# AgitPOV_WiFi.net
KiCad netlist of a schematic drawn in EAGLE
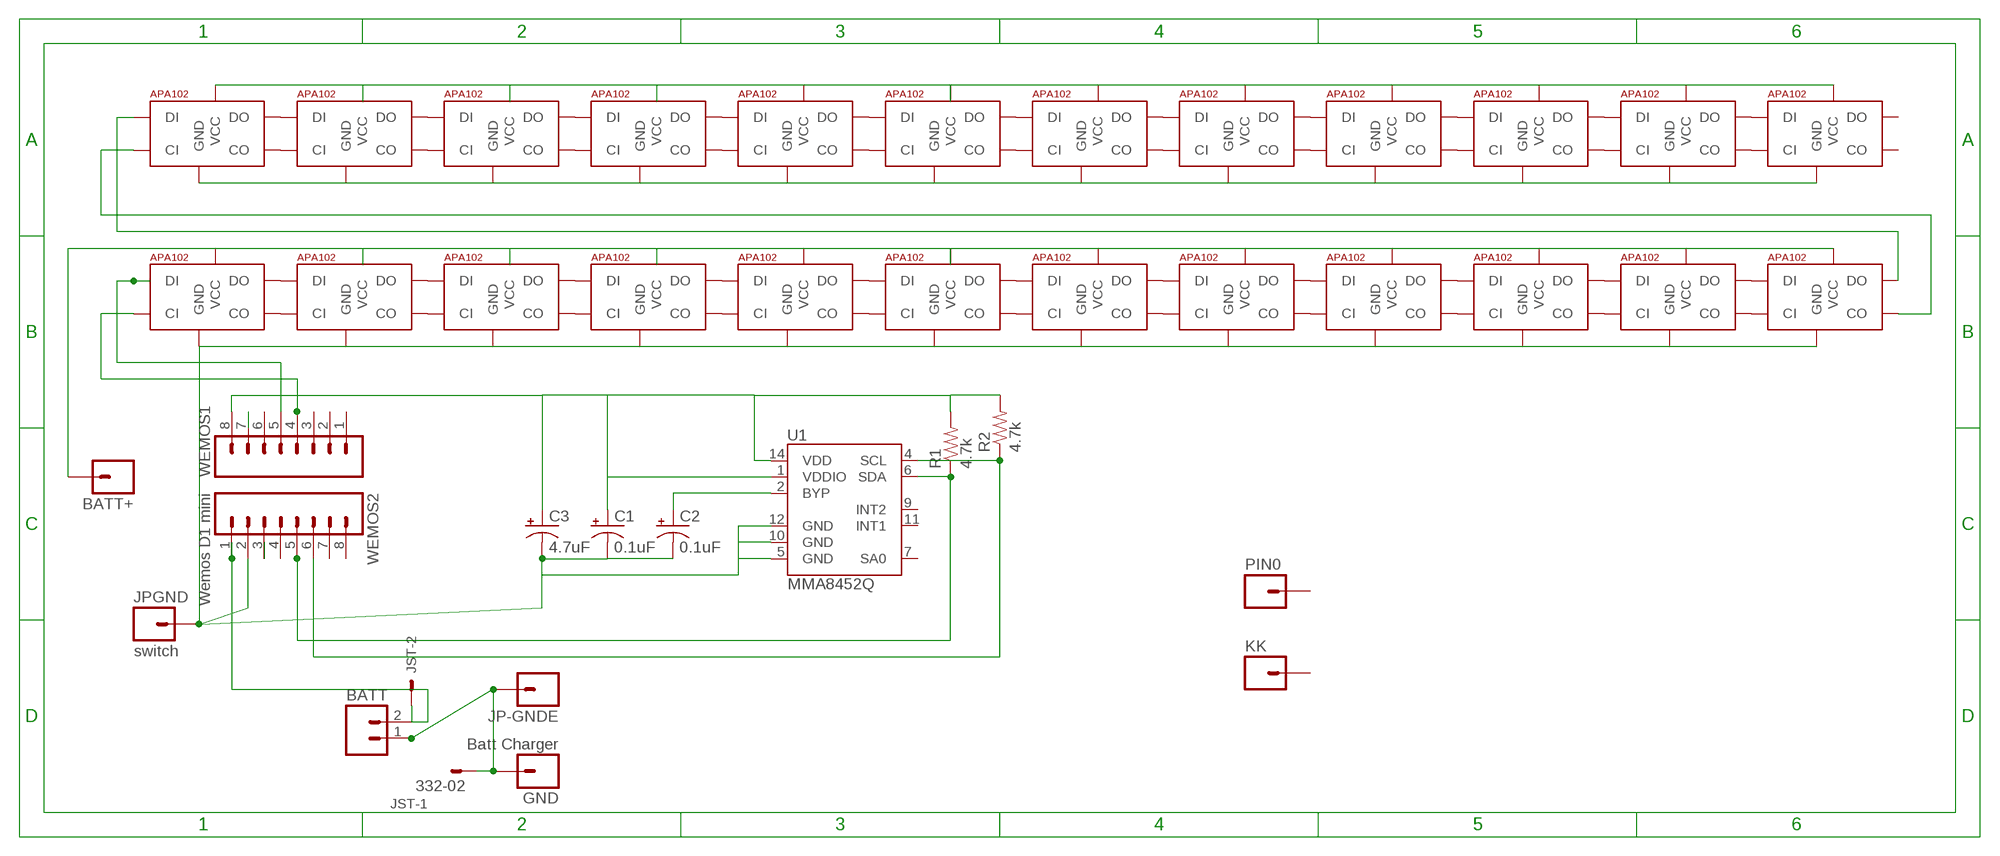
[diagram p0: schematic, sheet 1]

(export (version "E")
  (design (tool "Eeschema 10.0.6"))
  (components
    (comp (ref "BATT")
      (value "M02LOCK_LONGPADS")
      (footprint "eagle-import:1X02_LOCK_LONGPADS")
      (libsource (lib "eagle-import") (part "M02LOCK_LONGPADS"))
    )
    (comp (ref "BATT+")
      (value "M01PTH")
      (footprint "eagle-import:1X01")
      (libsource (lib "eagle-import") (part "M01PTH"))
    )
    (comp (ref "C1")
      (value "0.1uF")
      (footprint "eagle-import:EIA3216")
      (libsource (lib "eagle-import") (part "10UF-16V-10%(TANT)"))
    )
    (comp (ref "C2")
      (value "0.1uF")
      (footprint "eagle-import:EIA3216")
      (libsource (lib "eagle-import") (part "10UF-16V-10%(TANT)"))
    )
    (comp (ref "C3")
      (value "4.7uF")
      (footprint "eagle-import:EIA3216")
      (libsource (lib "eagle-import") (part "10UF-16V-10%(TANT)"))
    )
    (comp (ref "DEL1")
      (value "APA1025050")
      (footprint "eagle-import:APA102_5050")
      (libsource (lib "eagle-import") (part "APA1025050"))
    )
    (comp (ref "DEL2")
      (value "APA1025050")
      (footprint "eagle-import:APA102_5050")
      (libsource (lib "eagle-import") (part "APA1025050"))
    )
    (comp (ref "DEL3")
      (value "APA1025050")
      (footprint "eagle-import:APA102_5050")
      (libsource (lib "eagle-import") (part "APA1025050"))
    )
    (comp (ref "DEL4")
      (value "APA1025050")
      (footprint "eagle-import:APA102_5050")
      (libsource (lib "eagle-import") (part "APA1025050"))
    )
    (comp (ref "DEL5")
      (value "APA1025050")
      (footprint "eagle-import:APA102_5050")
      (libsource (lib "eagle-import") (part "APA1025050"))
    )
    (comp (ref "DEL6")
      (value "APA1025050")
      (footprint "eagle-import:APA102_5050")
      (libsource (lib "eagle-import") (part "APA1025050"))
    )
    (comp (ref "DEL7")
      (value "APA1025050")
      (footprint "eagle-import:APA102_5050")
      (libsource (lib "eagle-import") (part "APA1025050"))
    )
    (comp (ref "DEL8")
      (value "APA1025050")
      (footprint "eagle-import:APA102_5050")
      (libsource (lib "eagle-import") (part "APA1025050"))
    )
    (comp (ref "DEL9")
      (value "APA1025050")
      (footprint "eagle-import:APA102_5050")
      (libsource (lib "eagle-import") (part "APA1025050"))
    )
    (comp (ref "DEL10")
      (value "APA1025050")
      (footprint "eagle-import:APA102_5050")
      (libsource (lib "eagle-import") (part "APA1025050"))
    )
    (comp (ref "DEL11")
      (value "APA1025050")
      (footprint "eagle-import:APA102_5050")
      (libsource (lib "eagle-import") (part "APA1025050"))
    )
    (comp (ref "DEL12")
      (value "APA1025050")
      (footprint "eagle-import:APA102_5050")
      (libsource (lib "eagle-import") (part "APA1025050"))
    )
    (comp (ref "DEL13")
      (value "APA1025050")
      (footprint "eagle-import:APA102_5050")
      (libsource (lib "eagle-import") (part "APA1025050"))
    )
    (comp (ref "DEL15")
      (value "APA1025050")
      (footprint "eagle-import:APA102_5050")
      (libsource (lib "eagle-import") (part "APA1025050"))
    )
    (comp (ref "DEL16")
      (value "APA1025050")
      (footprint "eagle-import:APA102_5050")
      (libsource (lib "eagle-import") (part "APA1025050"))
    )
    (comp (ref "DEL17")
      (value "APA1025050")
      (footprint "eagle-import:APA102_5050")
      (libsource (lib "eagle-import") (part "APA1025050"))
    )
    (comp (ref "DEL18")
      (value "APA1025050")
      (footprint "eagle-import:APA102_5050")
      (libsource (lib "eagle-import") (part "APA1025050"))
    )
    (comp (ref "DEL19")
      (value "APA1025050")
      (footprint "eagle-import:APA102_5050")
      (libsource (lib "eagle-import") (part "APA1025050"))
    )
    (comp (ref "DEL20")
      (value "APA1025050")
      (footprint "eagle-import:APA102_5050")
      (libsource (lib "eagle-import") (part "APA1025050"))
    )
    (comp (ref "DEL21")
      (value "APA1025050")
      (footprint "eagle-import:APA102_5050")
      (libsource (lib "eagle-import") (part "APA1025050"))
    )
    (comp (ref "DEL22")
      (value "APA1025050")
      (footprint "eagle-import:APA102_5050")
      (libsource (lib "eagle-import") (part "APA1025050"))
    )
    (comp (ref "DEL23")
      (value "APA1025050")
      (footprint "eagle-import:APA102_5050")
      (libsource (lib "eagle-import") (part "APA1025050"))
    )
    (comp (ref "DEL24")
      (value "APA1025050")
      (footprint "eagle-import:APA102_5050")
      (libsource (lib "eagle-import") (part "APA1025050"))
    )
    (comp (ref "FFFFF")
      (value "APA1025050")
      (footprint "eagle-import:APA102_5050")
      (libsource (lib "eagle-import") (part "APA1025050"))
    )
    (comp (ref "GND")
      (value "Batt Charger")
      (footprint "eagle-import:1X01")
      (libsource (lib "eagle-import") (part "M01PTH"))
    )
    (comp (ref "JP-GNDE")
      (value "M01PTH")
      (footprint "eagle-import:1X01")
      (libsource (lib "eagle-import") (part "M01PTH"))
    )
    (comp (ref "JPGND")
      (value "switch")
      (footprint "eagle-import:1X01")
      (libsource (lib "eagle-import") (part "M01PTH"))
    )
    (comp (ref "JST")
      (value "332-02")
      (footprint "eagle-import:332-02")
      (libsource (lib "eagle-import") (part "332-02"))
    )
    (comp (ref "KK")
      (value "M01PTH")
      (footprint "eagle-import:1X01")
      (libsource (lib "eagle-import") (part "M01PTH"))
    )
    (comp (ref "PIN0")
      (value "M01PTH")
      (footprint "eagle-import:1X01")
      (libsource (lib "eagle-import") (part "M01PTH"))
    )
    (comp (ref "R1")
      (value "4.7k")
      (footprint "eagle-import:1206")
      (libsource (lib "eagle-import") (part "RESISTOR1206"))
    )
    (comp (ref "R2")
      (value "4.7k")
      (footprint "eagle-import:1206")
      (libsource (lib "eagle-import") (part "RESISTOR1206"))
    )
    (comp (ref "U1")
      (value "MMA8452Q")
      (footprint "eagle-import:QFN-16_0.5MM")
      (libsource (lib "eagle-import") (part "MMA8452Q"))
    )
    (comp (ref "WEMOS1")
      (value "M08")
      (footprint "eagle-import:1X08_ROUND")
      (libsource (lib "eagle-import") (part "M08"))
    )
    (comp (ref "WEMOS2")
      (value "Wemos D1 mini")
      (footprint "eagle-import:1X08_ROUND")
      (libsource (lib "eagle-import") (part "M08"))
    )
  )
  (nets
    (net (code "1") (name "/5V") (class "Default")
      (node (ref "BATT") (pin "2") (pinfunction "2_2") (pintype "passive"))
      (node (ref "BATT+") (pin "1") (pinfunction "1_1") (pintype "passive"))
      (node (ref "DEL1") (pin "1") (pinfunction "VCC_1") (pintype "bidirectional"))
      (node (ref "DEL10") (pin "1") (pinfunction "VCC_1") (pintype "bidirectional"))
      (node (ref "DEL11") (pin "1") (pinfunction "VCC_1") (pintype "bidirectional"))
      (node (ref "DEL12") (pin "1") (pinfunction "VCC_1") (pintype "bidirectional"))
      (node (ref "DEL13") (pin "1") (pinfunction "VCC_1") (pintype "bidirectional"))
      (node (ref "DEL15") (pin "1") (pinfunction "VCC_1") (pintype "bidirectional"))
      (node (ref "DEL16") (pin "1") (pinfunction "VCC_1") (pintype "bidirectional"))
      (node (ref "DEL17") (pin "1") (pinfunction "VCC_1") (pintype "bidirectional"))
      (node (ref "DEL18") (pin "1") (pinfunction "VCC_1") (pintype "bidirectional"))
      (node (ref "DEL19") (pin "1") (pinfunction "VCC_1") (pintype "bidirectional"))
      (node (ref "DEL2") (pin "1") (pinfunction "VCC_1") (pintype "bidirectional"))
      (node (ref "DEL20") (pin "1") (pinfunction "VCC_1") (pintype "bidirectional"))
      (node (ref "DEL21") (pin "1") (pinfunction "VCC_1") (pintype "bidirectional"))
      (node (ref "DEL22") (pin "1") (pinfunction "VCC_1") (pintype "bidirectional"))
      (node (ref "DEL23") (pin "1") (pinfunction "VCC_1") (pintype "bidirectional"))
      (node (ref "DEL24") (pin "1") (pinfunction "VCC_1") (pintype "bidirectional"))
      (node (ref "DEL3") (pin "1") (pinfunction "VCC_1") (pintype "bidirectional"))
      (node (ref "DEL4") (pin "1") (pinfunction "VCC_1") (pintype "bidirectional"))
      (node (ref "DEL5") (pin "1") (pinfunction "VCC_1") (pintype "bidirectional"))
      (node (ref "DEL6") (pin "1") (pinfunction "VCC_1") (pintype "bidirectional"))
      (node (ref "DEL7") (pin "1") (pinfunction "VCC_1") (pintype "bidirectional"))
      (node (ref "DEL8") (pin "1") (pinfunction "VCC_1") (pintype "bidirectional"))
      (node (ref "DEL9") (pin "1") (pinfunction "VCC_1") (pintype "bidirectional"))
      (node (ref "FFFFF") (pin "1") (pinfunction "VCC_1") (pintype "bidirectional"))
      (node (ref "JST") (pin "2") (pinfunction "S_2") (pintype "passive"))
      (node (ref "WEMOS2") (pin "1") (pinfunction "1_1") (pintype "passive"))
    )
    (net (code "2") (name "/GND") (class "Default")
      (node (ref "C1") (pin "C") (pinfunction "-_C") (pintype "passive"))
      (node (ref "C2") (pin "C") (pinfunction "-_C") (pintype "passive"))
      (node (ref "C3") (pin "C") (pinfunction "-_C") (pintype "passive"))
      (node (ref "DEL1") (pin "6") (pinfunction "GND_6") (pintype "bidirectional"))
      (node (ref "DEL10") (pin "6") (pinfunction "GND_6") (pintype "bidirectional"))
      (node (ref "DEL11") (pin "6") (pinfunction "GND_6") (pintype "bidirectional"))
      (node (ref "DEL12") (pin "6") (pinfunction "GND_6") (pintype "bidirectional"))
      (node (ref "DEL13") (pin "6") (pinfunction "GND_6") (pintype "bidirectional"))
      (node (ref "DEL15") (pin "6") (pinfunction "GND_6") (pintype "bidirectional"))
      (node (ref "DEL16") (pin "6") (pinfunction "GND_6") (pintype "bidirectional"))
      (node (ref "DEL17") (pin "6") (pinfunction "GND_6") (pintype "bidirectional"))
      (node (ref "DEL18") (pin "6") (pinfunction "GND_6") (pintype "bidirectional"))
      (node (ref "DEL19") (pin "6") (pinfunction "GND_6") (pintype "bidirectional"))
      (node (ref "DEL2") (pin "6") (pinfunction "GND_6") (pintype "bidirectional"))
      (node (ref "DEL20") (pin "6") (pinfunction "GND_6") (pintype "bidirectional"))
      (node (ref "DEL21") (pin "6") (pinfunction "GND_6") (pintype "bidirectional"))
      (node (ref "DEL22") (pin "6") (pinfunction "GND_6") (pintype "bidirectional"))
      (node (ref "DEL23") (pin "6") (pinfunction "GND_6") (pintype "bidirectional"))
      (node (ref "DEL24") (pin "6") (pinfunction "GND_6") (pintype "bidirectional"))
      (node (ref "DEL3") (pin "6") (pinfunction "GND_6") (pintype "bidirectional"))
      (node (ref "DEL4") (pin "6") (pinfunction "GND_6") (pintype "bidirectional"))
      (node (ref "DEL5") (pin "6") (pinfunction "GND_6") (pintype "bidirectional"))
      (node (ref "DEL6") (pin "6") (pinfunction "GND_6") (pintype "bidirectional"))
      (node (ref "DEL7") (pin "6") (pinfunction "GND_6") (pintype "bidirectional"))
      (node (ref "DEL8") (pin "6") (pinfunction "GND_6") (pintype "bidirectional"))
      (node (ref "DEL9") (pin "6") (pinfunction "GND_6") (pintype "bidirectional"))
      (node (ref "FFFFF") (pin "6") (pinfunction "GND_6") (pintype "bidirectional"))
      (node (ref "JPGND") (pin "1") (pinfunction "1_1") (pintype "passive"))
      (node (ref "U1") (pin "10") (pinfunction "GND_10") (pintype "bidirectional"))
      (node (ref "U1") (pin "12") (pinfunction "GND_12") (pintype "bidirectional"))
      (node (ref "U1") (pin "5") (pinfunction "GND_5") (pintype "bidirectional"))
      (node (ref "WEMOS2") (pin "2") (pinfunction "2_2") (pintype "passive"))
    )
    (net (code "3") (name "Net-(C1-+)") (class "Default")
      (node (ref "C1") (pin "A") (pinfunction "+_A") (pintype "passive"))
      (node (ref "C3") (pin "A") (pinfunction "+_A") (pintype "passive"))
      (node (ref "R1") (pin "2") (pinfunction "2_2") (pintype "passive"))
      (node (ref "R2") (pin "2") (pinfunction "2_2") (pintype "passive"))
      (node (ref "U1") (pin "1") (pinfunction "VDDIO_1") (pintype "bidirectional"))
      (node (ref "U1") (pin "14") (pinfunction "VDD_14") (pintype "bidirectional"))
      (node (ref "WEMOS1") (pin "8") (pinfunction "8_8") (pintype "passive"))
    )
    (net (code "4") (name "Net-(C2-+)") (class "Default")
      (node (ref "C2") (pin "A") (pinfunction "+_A") (pintype "passive"))
      (node (ref "U1") (pin "2") (pinfunction "BYP_2") (pintype "bidirectional"))
    )
    (net (code "5") (name "Net-(DEL1-CI)") (class "Default")
      (node (ref "DEL1") (pin "5") (pinfunction "CI_5") (pintype "bidirectional"))
      (node (ref "WEMOS1") (pin "4") (pinfunction "4_4") (pintype "passive"))
    )
    (net (code "6") (name "Net-(DEL1-CO)") (class "Default")
      (node (ref "DEL1") (pin "2") (pinfunction "CO_2") (pintype "bidirectional"))
      (node (ref "DEL2") (pin "5") (pinfunction "CI_5") (pintype "bidirectional"))
    )
    (net (code "7") (name "Net-(DEL1-DI)") (class "Default")
      (node (ref "DEL1") (pin "4") (pinfunction "DI_4") (pintype "bidirectional"))
      (node (ref "WEMOS1") (pin "5") (pinfunction "5_5") (pintype "passive"))
    )
    (net (code "8") (name "Net-(DEL1-DO)") (class "Default")
      (node (ref "DEL1") (pin "3") (pinfunction "DO_3") (pintype "bidirectional"))
      (node (ref "DEL2") (pin "4") (pinfunction "DI_4") (pintype "bidirectional"))
    )
    (net (code "9") (name "Net-(DEL2-CO)") (class "Default")
      (node (ref "DEL2") (pin "2") (pinfunction "CO_2") (pintype "bidirectional"))
      (node (ref "DEL3") (pin "5") (pinfunction "CI_5") (pintype "bidirectional"))
    )
    (net (code "10") (name "Net-(DEL2-DO)") (class "Default")
      (node (ref "DEL2") (pin "3") (pinfunction "DO_3") (pintype "bidirectional"))
      (node (ref "DEL3") (pin "4") (pinfunction "DI_4") (pintype "bidirectional"))
    )
    (net (code "11") (name "Net-(DEL3-CO)") (class "Default")
      (node (ref "DEL3") (pin "2") (pinfunction "CO_2") (pintype "bidirectional"))
      (node (ref "DEL4") (pin "5") (pinfunction "CI_5") (pintype "bidirectional"))
    )
    (net (code "12") (name "Net-(DEL3-DO)") (class "Default")
      (node (ref "DEL3") (pin "3") (pinfunction "DO_3") (pintype "bidirectional"))
      (node (ref "DEL4") (pin "4") (pinfunction "DI_4") (pintype "bidirectional"))
    )
    (net (code "13") (name "Net-(DEL4-CO)") (class "Default")
      (node (ref "DEL4") (pin "2") (pinfunction "CO_2") (pintype "bidirectional"))
      (node (ref "DEL5") (pin "5") (pinfunction "CI_5") (pintype "bidirectional"))
    )
    (net (code "14") (name "Net-(DEL4-DO)") (class "Default")
      (node (ref "DEL4") (pin "3") (pinfunction "DO_3") (pintype "bidirectional"))
      (node (ref "DEL5") (pin "4") (pinfunction "DI_4") (pintype "bidirectional"))
    )
    (net (code "15") (name "Net-(DEL5-CO)") (class "Default")
      (node (ref "DEL5") (pin "2") (pinfunction "CO_2") (pintype "bidirectional"))
      (node (ref "DEL6") (pin "5") (pinfunction "CI_5") (pintype "bidirectional"))
    )
    (net (code "16") (name "Net-(DEL5-DO)") (class "Default")
      (node (ref "DEL5") (pin "3") (pinfunction "DO_3") (pintype "bidirectional"))
      (node (ref "DEL6") (pin "4") (pinfunction "DI_4") (pintype "bidirectional"))
    )
    (net (code "17") (name "Net-(DEL6-CO)") (class "Default")
      (node (ref "DEL6") (pin "2") (pinfunction "CO_2") (pintype "bidirectional"))
      (node (ref "DEL7") (pin "5") (pinfunction "CI_5") (pintype "bidirectional"))
    )
    (net (code "18") (name "Net-(DEL6-DO)") (class "Default")
      (node (ref "DEL6") (pin "3") (pinfunction "DO_3") (pintype "bidirectional"))
      (node (ref "DEL7") (pin "4") (pinfunction "DI_4") (pintype "bidirectional"))
    )
    (net (code "19") (name "Net-(DEL7-CO)") (class "Default")
      (node (ref "DEL7") (pin "2") (pinfunction "CO_2") (pintype "bidirectional"))
      (node (ref "DEL8") (pin "5") (pinfunction "CI_5") (pintype "bidirectional"))
    )
    (net (code "20") (name "Net-(DEL7-DO)") (class "Default")
      (node (ref "DEL7") (pin "3") (pinfunction "DO_3") (pintype "bidirectional"))
      (node (ref "DEL8") (pin "4") (pinfunction "DI_4") (pintype "bidirectional"))
    )
    (net (code "21") (name "Net-(DEL8-CO)") (class "Default")
      (node (ref "DEL8") (pin "2") (pinfunction "CO_2") (pintype "bidirectional"))
      (node (ref "DEL9") (pin "5") (pinfunction "CI_5") (pintype "bidirectional"))
    )
    (net (code "22") (name "Net-(DEL8-DO)") (class "Default")
      (node (ref "DEL8") (pin "3") (pinfunction "DO_3") (pintype "bidirectional"))
      (node (ref "DEL9") (pin "4") (pinfunction "DI_4") (pintype "bidirectional"))
    )
    (net (code "23") (name "Net-(DEL10-CI)") (class "Default")
      (node (ref "DEL10") (pin "5") (pinfunction "CI_5") (pintype "bidirectional"))
      (node (ref "DEL9") (pin "2") (pinfunction "CO_2") (pintype "bidirectional"))
    )
    (net (code "24") (name "Net-(DEL10-CO)") (class "Default")
      (node (ref "DEL10") (pin "2") (pinfunction "CO_2") (pintype "bidirectional"))
      (node (ref "DEL11") (pin "5") (pinfunction "CI_5") (pintype "bidirectional"))
    )
    (net (code "25") (name "Net-(DEL10-DI)") (class "Default")
      (node (ref "DEL10") (pin "4") (pinfunction "DI_4") (pintype "bidirectional"))
      (node (ref "DEL9") (pin "3") (pinfunction "DO_3") (pintype "bidirectional"))
    )
    (net (code "26") (name "Net-(DEL10-DO)") (class "Default")
      (node (ref "DEL10") (pin "3") (pinfunction "DO_3") (pintype "bidirectional"))
      (node (ref "DEL11") (pin "4") (pinfunction "DI_4") (pintype "bidirectional"))
    )
    (net (code "27") (name "Net-(DEL11-CO)") (class "Default")
      (node (ref "DEL11") (pin "2") (pinfunction "CO_2") (pintype "bidirectional"))
      (node (ref "DEL12") (pin "5") (pinfunction "CI_5") (pintype "bidirectional"))
    )
    (net (code "28") (name "Net-(DEL11-DO)") (class "Default")
      (node (ref "DEL11") (pin "3") (pinfunction "DO_3") (pintype "bidirectional"))
      (node (ref "DEL12") (pin "4") (pinfunction "DI_4") (pintype "bidirectional"))
    )
    (net (code "29") (name "Net-(DEL12-CO)") (class "Default")
      (node (ref "DEL12") (pin "2") (pinfunction "CO_2") (pintype "bidirectional"))
      (node (ref "DEL13") (pin "5") (pinfunction "CI_5") (pintype "bidirectional"))
    )
    (net (code "30") (name "Net-(DEL12-DO)") (class "Default")
      (node (ref "DEL12") (pin "3") (pinfunction "DO_3") (pintype "bidirectional"))
      (node (ref "DEL13") (pin "4") (pinfunction "DI_4") (pintype "bidirectional"))
    )
    (net (code "31") (name "Net-(DEL13-CO)") (class "Default")
      (node (ref "DEL13") (pin "2") (pinfunction "CO_2") (pintype "bidirectional"))
      (node (ref "FFFFF") (pin "5") (pinfunction "CI_5") (pintype "bidirectional"))
    )
    (net (code "32") (name "Net-(DEL13-DO)") (class "Default")
      (node (ref "DEL13") (pin "3") (pinfunction "DO_3") (pintype "bidirectional"))
      (node (ref "FFFFF") (pin "4") (pinfunction "DI_4") (pintype "bidirectional"))
    )
    (net (code "33") (name "Net-(DEL15-CI)") (class "Default")
      (node (ref "DEL15") (pin "5") (pinfunction "CI_5") (pintype "bidirectional"))
      (node (ref "FFFFF") (pin "2") (pinfunction "CO_2") (pintype "bidirectional"))
    )
    (net (code "34") (name "Net-(DEL15-CO)") (class "Default")
      (node (ref "DEL15") (pin "2") (pinfunction "CO_2") (pintype "bidirectional"))
      (node (ref "DEL16") (pin "5") (pinfunction "CI_5") (pintype "bidirectional"))
    )
    (net (code "35") (name "Net-(DEL15-DI)") (class "Default")
      (node (ref "DEL15") (pin "4") (pinfunction "DI_4") (pintype "bidirectional"))
      (node (ref "FFFFF") (pin "3") (pinfunction "DO_3") (pintype "bidirectional"))
    )
    (net (code "36") (name "Net-(DEL15-DO)") (class "Default")
      (node (ref "DEL15") (pin "3") (pinfunction "DO_3") (pintype "bidirectional"))
      (node (ref "DEL16") (pin "4") (pinfunction "DI_4") (pintype "bidirectional"))
    )
    (net (code "37") (name "Net-(DEL16-CO)") (class "Default")
      (node (ref "DEL16") (pin "2") (pinfunction "CO_2") (pintype "bidirectional"))
      (node (ref "DEL17") (pin "5") (pinfunction "CI_5") (pintype "bidirectional"))
    )
    (net (code "38") (name "Net-(DEL16-DO)") (class "Default")
      (node (ref "DEL16") (pin "3") (pinfunction "DO_3") (pintype "bidirectional"))
      (node (ref "DEL17") (pin "4") (pinfunction "DI_4") (pintype "bidirectional"))
    )
    (net (code "39") (name "Net-(DEL17-CO)") (class "Default")
      (node (ref "DEL17") (pin "2") (pinfunction "CO_2") (pintype "bidirectional"))
      (node (ref "DEL18") (pin "5") (pinfunction "CI_5") (pintype "bidirectional"))
    )
    (net (code "40") (name "Net-(DEL17-DO)") (class "Default")
      (node (ref "DEL17") (pin "3") (pinfunction "DO_3") (pintype "bidirectional"))
      (node (ref "DEL18") (pin "4") (pinfunction "DI_4") (pintype "bidirectional"))
    )
    (net (code "41") (name "Net-(DEL18-CO)") (class "Default")
      (node (ref "DEL18") (pin "2") (pinfunction "CO_2") (pintype "bidirectional"))
      (node (ref "DEL19") (pin "5") (pinfunction "CI_5") (pintype "bidirectional"))
    )
    (net (code "42") (name "Net-(DEL18-DO)") (class "Default")
      (node (ref "DEL18") (pin "3") (pinfunction "DO_3") (pintype "bidirectional"))
      (node (ref "DEL19") (pin "4") (pinfunction "DI_4") (pintype "bidirectional"))
    )
    (net (code "43") (name "Net-(DEL19-CO)") (class "Default")
      (node (ref "DEL19") (pin "2") (pinfunction "CO_2") (pintype "bidirectional"))
      (node (ref "DEL20") (pin "5") (pinfunction "CI_5") (pintype "bidirectional"))
    )
    (net (code "44") (name "Net-(DEL19-DO)") (class "Default")
      (node (ref "DEL19") (pin "3") (pinfunction "DO_3") (pintype "bidirectional"))
      (node (ref "DEL20") (pin "4") (pinfunction "DI_4") (pintype "bidirectional"))
    )
    (net (code "45") (name "Net-(DEL20-CO)") (class "Default")
      (node (ref "DEL20") (pin "2") (pinfunction "CO_2") (pintype "bidirectional"))
      (node (ref "DEL21") (pin "5") (pinfunction "CI_5") (pintype "bidirectional"))
    )
    (net (code "46") (name "Net-(DEL20-DO)") (class "Default")
      (node (ref "DEL20") (pin "3") (pinfunction "DO_3") (pintype "bidirectional"))
      (node (ref "DEL21") (pin "4") (pinfunction "DI_4") (pintype "bidirectional"))
    )
    (net (code "47") (name "Net-(DEL21-CO)") (class "Default")
      (node (ref "DEL21") (pin "2") (pinfunction "CO_2") (pintype "bidirectional"))
      (node (ref "DEL22") (pin "5") (pinfunction "CI_5") (pintype "bidirectional"))
    )
    (net (code "48") (name "Net-(DEL21-DO)") (class "Default")
      (node (ref "DEL21") (pin "3") (pinfunction "DO_3") (pintype "bidirectional"))
      (node (ref "DEL22") (pin "4") (pinfunction "DI_4") (pintype "bidirectional"))
    )
    (net (code "49") (name "Net-(DEL22-CO)") (class "Default")
      (node (ref "DEL22") (pin "2") (pinfunction "CO_2") (pintype "bidirectional"))
      (node (ref "DEL23") (pin "5") (pinfunction "CI_5") (pintype "bidirectional"))
    )
    (net (code "50") (name "Net-(DEL22-DO)") (class "Default")
      (node (ref "DEL22") (pin "3") (pinfunction "DO_3") (pintype "bidirectional"))
      (node (ref "DEL23") (pin "4") (pinfunction "DI_4") (pintype "bidirectional"))
    )
    (net (code "51") (name "Net-(DEL23-CO)") (class "Default")
      (node (ref "DEL23") (pin "2") (pinfunction "CO_2") (pintype "bidirectional"))
      (node (ref "DEL24") (pin "5") (pinfunction "CI_5") (pintype "bidirectional"))
    )
    (net (code "52") (name "Net-(DEL23-DO)") (class "Default")
      (node (ref "DEL23") (pin "3") (pinfunction "DO_3") (pintype "bidirectional"))
      (node (ref "DEL24") (pin "4") (pinfunction "DI_4") (pintype "bidirectional"))
    )
    (net (code "53") (name "Net-(JSTA-S)") (class "Default")
      (node (ref "BATT") (pin "1") (pinfunction "1_1") (pintype "passive"))
      (node (ref "GND") (pin "1") (pinfunction "1_1") (pintype "passive"))
      (node (ref "JP-GNDE") (pin "1") (pinfunction "1_1") (pintype "passive"))
      (node (ref "JST") (pin "1") (pinfunction "S_1") (pintype "passive"))
    )
    (net (code "54") (name "Net-(U1-SCL)") (class "Default")
      (node (ref "R2") (pin "1") (pinfunction "1_1") (pintype "passive"))
      (node (ref "U1") (pin "4") (pinfunction "SCL_4") (pintype "bidirectional"))
      (node (ref "WEMOS2") (pin "6") (pinfunction "6_6") (pintype "passive"))
    )
    (net (code "55") (name "Net-(U1-SDA)") (class "Default")
      (node (ref "R1") (pin "1") (pinfunction "1_1") (pintype "passive"))
      (node (ref "U1") (pin "6") (pinfunction "SDA_6") (pintype "bidirectional"))
      (node (ref "WEMOS2") (pin "5") (pinfunction "5_5") (pintype "passive"))
    )
    (net (code "56") (name "unconnected-(DEL24-CO-Pad2)") (class "Default")
      (node (ref "DEL24") (pin "2") (pinfunction "CO_2") (pintype "bidirectional"))
    )
    (net (code "57") (name "unconnected-(DEL24-DO-Pad3)") (class "Default")
      (node (ref "DEL24") (pin "3") (pinfunction "DO_3") (pintype "bidirectional"))
    )
    (net (code "58") (name "unconnected-(KK-Pad1)") (class "Default")
      (node (ref "KK") (pin "1") (pinfunction "1_1") (pintype "passive"))
    )
    (net (code "59") (name "unconnected-(PIN0-Pad1)") (class "Default")
      (node (ref "PIN0") (pin "1") (pinfunction "1_1") (pintype "passive"))
    )
    (net (code "60") (name "unconnected-(U1-INT1-Pad11)") (class "Default")
      (node (ref "U1") (pin "11") (pinfunction "INT1_11") (pintype "bidirectional"))
    )
    (net (code "61") (name "unconnected-(U1-INT2-Pad9)") (class "Default")
      (node (ref "U1") (pin "9") (pinfunction "INT2_9") (pintype "bidirectional"))
    )
    (net (code "62") (name "unconnected-(U1-SA0-Pad7)") (class "Default")
      (node (ref "U1") (pin "7") (pinfunction "SA0_7") (pintype "bidirectional"))
    )
    (net (code "63") (name "unconnected-(WEMOS1-Pad1)") (class "Default")
      (node (ref "WEMOS1") (pin "1") (pinfunction "1_1") (pintype "passive"))
    )
    (net (code "64") (name "unconnected-(WEMOS1-Pad2)") (class "Default")
      (node (ref "WEMOS1") (pin "2") (pinfunction "2_2") (pintype "passive"))
    )
    (net (code "65") (name "unconnected-(WEMOS1-Pad3)") (class "Default")
      (node (ref "WEMOS1") (pin "3") (pinfunction "3_3") (pintype "passive"))
    )
    (net (code "66") (name "unconnected-(WEMOS1-Pad6)") (class "Default")
      (node (ref "WEMOS1") (pin "6") (pinfunction "6_6") (pintype "passive"))
    )
    (net (code "67") (name "unconnected-(WEMOS1-Pad7)") (class "Default")
      (node (ref "WEMOS1") (pin "7") (pinfunction "7_7") (pintype "passive"))
    )
    (net (code "68") (name "unconnected-(WEMOS2-Pad3)") (class "Default")
      (node (ref "WEMOS2") (pin "3") (pinfunction "3_3") (pintype "passive"))
    )
    (net (code "69") (name "unconnected-(WEMOS2-Pad4)") (class "Default")
      (node (ref "WEMOS2") (pin "4") (pinfunction "4_4") (pintype "passive"))
    )
    (net (code "70") (name "unconnected-(WEMOS2-Pad7)") (class "Default")
      (node (ref "WEMOS2") (pin "7") (pinfunction "7_7") (pintype "passive"))
    )
    (net (code "71") (name "unconnected-(WEMOS2-Pad8)") (class "Default")
      (node (ref "WEMOS2") (pin "8") (pinfunction "8_8") (pintype "passive"))
    )
  )
)
